# 5_-COM.net
KiCad netlist of a schematic drawn in Altium Designer
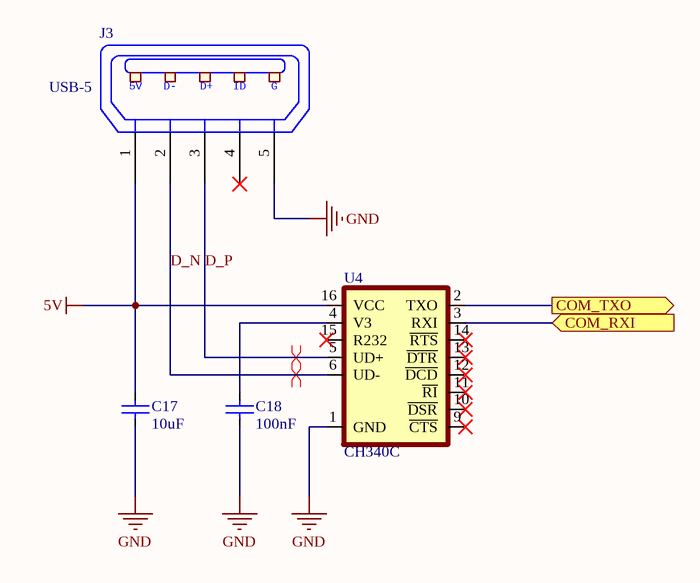
[diagram p0: [5]-COM.SchDoc]

(export (version "E")
  (design (tool "Eeschema 10.0.6"))
  (components
    (comp (ref "C17")
      (value "10uF")
      (footprint "CAP_0805")
      (description "Capacitor")
      (fields (field (name "PUBLISHER") "Altium Limited"))
      (libsource (lib "My Library") (part "CapSMD"))
    )
    (comp (ref "C18")
      (value "100nF")
      (footprint "CAP_0805")
      (description "Capacitor")
      (fields (field (name "PUBLISHER") "Altium Limited"))
      (libsource (lib "My Library") (part "CapSMD"))
    )
    (comp (ref "J3")
      (value "USB-5")
      (footprint "USB-M1")
      (fields
        (field (name "MANUFACTURER") "FCI")
        (field (name "MANUFACTURER PART NUMBER") "10118193-0001LF")
        (field (name ".CREATOR") "MM")
        (field (name ".CHECKED PCB") "RF")
        (field (name ".CHECKED SCH") "MM")
      )
      (libsource (lib "My Library") (part "USB-5"))
    )
    (comp (ref "U4")
      (value "CH340C")
      (footprint "SO16")
      (description "USB to serial chip CH340")
      (fields (field (name "MF") "WCH"))
      (libsource (lib "My Library") (part "CH340C"))
    )
  )
  (nets
    (net (code "1") (name "/COM_RXI") (class "Default")
      (node (ref "U4") (pin "3") (pinfunction "RXI_3") (pintype "bidirectional"))
    )
    (net (code "2") (name "/COM_TXO") (class "Default")
      (node (ref "U4") (pin "2") (pinfunction "TXO_2") (pintype "bidirectional"))
    )
    (net (code "3") (name "/D_N") (class "Default")
      (node (ref "J3") (pin "2") (pinfunction "P2_2") (pintype "passive"))
      (node (ref "U4") (pin "6") (pinfunction "UD-_6") (pintype "bidirectional"))
    )
    (net (code "4") (name "/D_P") (class "Default")
      (node (ref "J3") (pin "3") (pinfunction "P3_3") (pintype "passive"))
      (node (ref "U4") (pin "5") (pinfunction "UD+_5") (pintype "bidirectional"))
    )
    (net (code "5") (name "5V") (class "Default")
      (node (ref "C17") (pin "2") (pinfunction "2_2") (pintype "passive"))
      (node (ref "J3") (pin "1") (pinfunction "P1_1") (pintype "passive"))
      (node (ref "U4") (pin "16") (pinfunction "VCC_16") (pintype "bidirectional"))
    )
    (net (code "6") (name "GND") (class "Default")
      (node (ref "C17") (pin "1") (pinfunction "1_1") (pintype "passive"))
      (node (ref "C18") (pin "1") (pinfunction "1_1") (pintype "passive"))
      (node (ref "J3") (pin "5") (pinfunction "P5_5") (pintype "passive"))
      (node (ref "U4") (pin "1") (pinfunction "GND_1") (pintype "bidirectional"))
    )
    (net (code "7") (name "Net-(U4-V3)") (class "Default")
      (node (ref "C18") (pin "2") (pinfunction "2_2") (pintype "passive"))
      (node (ref "U4") (pin "4") (pinfunction "V3_4") (pintype "bidirectional"))
    )
    (net (code "8") (name "unconnected-(J3-P4-Pad4)") (class "Default")
      (node (ref "J3") (pin "4") (pinfunction "P4_4") (pintype "passive+no_connect"))
    )
    (net (code "9") (name "unconnected-(U4-R232-Pad15)") (class "Default")
      (node (ref "U4") (pin "15") (pinfunction "R232_15") (pintype "bidirectional+no_connect"))
    )
    (net (code "10") (name "unconnected-(U4-~{CTS}-Pad9)") (class "Default")
      (node (ref "U4") (pin "9") (pinfunction "~{CTS}_9") (pintype "bidirectional+no_connect"))
    )
    (net (code "11") (name "unconnected-(U4-~{DCD}-Pad12)") (class "Default")
      (node (ref "U4") (pin "12") (pinfunction "~{DCD}_12") (pintype "bidirectional+no_connect"))
    )
    (net (code "12") (name "unconnected-(U4-~{DSR}-Pad10)") (class "Default")
      (node (ref "U4") (pin "10") (pinfunction "~{DSR}_10") (pintype "bidirectional+no_connect"))
    )
    (net (code "13") (name "unconnected-(U4-~{DTR}-Pad13)") (class "Default")
      (node (ref "U4") (pin "13") (pinfunction "~{DTR}_13") (pintype "bidirectional+no_connect"))
    )
    (net (code "14") (name "unconnected-(U4-~{RI}-Pad11)") (class "Default")
      (node (ref "U4") (pin "11") (pinfunction "~{RI}_11") (pintype "bidirectional+no_connect"))
    )
    (net (code "15") (name "unconnected-(U4-~{RTS}-Pad14)") (class "Default")
      (node (ref "U4") (pin "14") (pinfunction "~{RTS}_14") (pintype "bidirectional+no_connect"))
    )
  )
)
